# Parallel_Input.net
KiCad netlist of a schematic drawn in Altium Designer
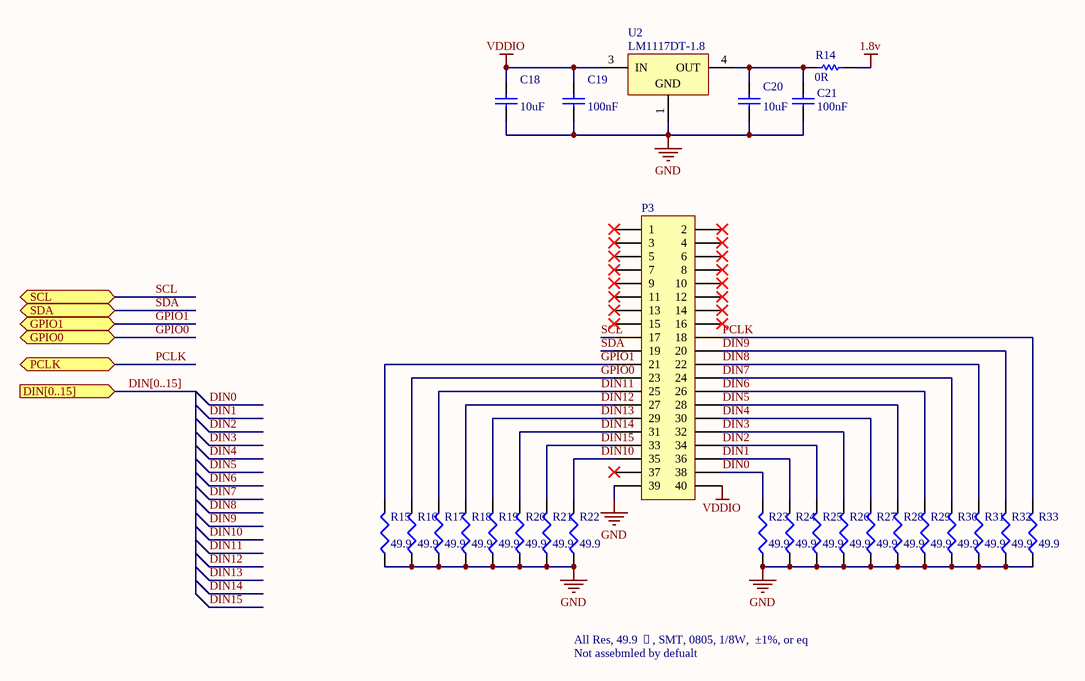
[diagram p0: Parallel Input.SchDoc]

(export (version "E")
  (design (tool "Eeschema 10.0.6"))
  (components
    (comp (ref "C18")
      (value "10uF")
      (footprint "0805")
      (description "Capacitor")
      (fields (field (name "PUBLISHER") "Altium Limited"))
      (libsource (lib "Miscellaneous Devices") (part "Cap"))
    )
    (comp (ref "C19")
      (value "100nF")
      (footprint "0603")
      (description "Capacitor")
      (fields (field (name "PUBLISHER") "Altium Limited"))
      (libsource (lib "Miscellaneous Devices") (part "Cap"))
    )
    (comp (ref "C20")
      (value "10uF")
      (footprint "0805")
      (description "Capacitor")
      (fields (field (name "PUBLISHER") "Altium Limited"))
      (libsource (lib "Miscellaneous Devices") (part "Cap"))
    )
    (comp (ref "C21")
      (value "100nF")
      (footprint "0603")
      (description "Capacitor")
      (fields (field (name "PUBLISHER") "Altium Limited"))
      (libsource (lib "Miscellaneous Devices") (part "Cap"))
    )
    (comp (ref "P3")
      (value "WE-2,54mm_Box Header 61204020621")
      (footprint "61204020621")
      (description "WR-BHD 2.54mm Male SMT Box Header")
      (fields
        (field (name "MANUFACTURER") "Würth Elektronik eiSos GmbH")
        (field (name "PARTNO") "61204020621")
        (field (name "CREATED BY") "Karrer Zheng")
      )
      (libsource (lib "WE_WR-BHD_Box Header_2.54mm_rev15b") (part "WE-2,54mm_Box Header 61204020621"))
    )
    (comp (ref "R14")
      (value "0R")
      (footprint "0805")
      (description "Semiconductor Resistor")
      (fields (field (name "PUBLISHER") "Altium Limited"))
      (libsource (lib "Miscellaneous Devices") (part "Res Semi"))
    )
    (comp (ref "R15")
      (value "49.9")
      (footprint "12Z-2010")
      (description "Resistor")
      (fields (field (name "Comment") "Res3") (field (name "PUBLISHER") "Altium Limited"))
      (libsource (lib "Miscellaneous Devices") (part "Res3"))
    )
    (comp (ref "R16")
      (value "49.9")
      (footprint "12Z-2010")
      (description "Resistor")
      (fields (field (name "Comment") "Res3") (field (name "PUBLISHER") "Altium Limited"))
      (libsource (lib "Miscellaneous Devices") (part "Res3"))
    )
    (comp (ref "R17")
      (value "49.9")
      (footprint "12Z-2010")
      (description "Resistor")
      (fields (field (name "Comment") "Res3") (field (name "PUBLISHER") "Altium Limited"))
      (libsource (lib "Miscellaneous Devices") (part "Res3"))
    )
    (comp (ref "R18")
      (value "49.9")
      (footprint "12Z-2010")
      (description "Resistor")
      (fields (field (name "Comment") "Res3") (field (name "PUBLISHER") "Altium Limited"))
      (libsource (lib "Miscellaneous Devices") (part "Res3"))
    )
    (comp (ref "R19")
      (value "49.9")
      (footprint "12Z-2010")
      (description "Resistor")
      (fields (field (name "Comment") "Res3") (field (name "PUBLISHER") "Altium Limited"))
      (libsource (lib "Miscellaneous Devices") (part "Res3"))
    )
    (comp (ref "R20")
      (value "49.9")
      (footprint "12Z-2010")
      (description "Resistor")
      (fields (field (name "Comment") "Res3") (field (name "PUBLISHER") "Altium Limited"))
      (libsource (lib "Miscellaneous Devices") (part "Res3"))
    )
    (comp (ref "R21")
      (value "49.9")
      (footprint "12Z-2010")
      (description "Resistor")
      (fields (field (name "Comment") "Res3") (field (name "PUBLISHER") "Altium Limited"))
      (libsource (lib "Miscellaneous Devices") (part "Res3"))
    )
    (comp (ref "R22")
      (value "49.9")
      (footprint "12Z-2010")
      (description "Resistor")
      (fields (field (name "Comment") "Res3") (field (name "PUBLISHER") "Altium Limited"))
      (libsource (lib "Miscellaneous Devices") (part "Res3"))
    )
    (comp (ref "R23")
      (value "49.9")
      (footprint "12Z-2010")
      (description "Resistor")
      (fields (field (name "Comment") "Res3") (field (name "PUBLISHER") "Altium Limited"))
      (libsource (lib "Miscellaneous Devices") (part "Res3"))
    )
    (comp (ref "R24")
      (value "49.9")
      (footprint "12Z-2010")
      (description "Resistor")
      (fields (field (name "Comment") "Res3") (field (name "PUBLISHER") "Altium Limited"))
      (libsource (lib "Miscellaneous Devices") (part "Res3"))
    )
    (comp (ref "R25")
      (value "49.9")
      (footprint "12Z-2010")
      (description "Resistor")
      (fields (field (name "Comment") "Res3") (field (name "PUBLISHER") "Altium Limited"))
      (libsource (lib "Miscellaneous Devices") (part "Res3"))
    )
    (comp (ref "R26")
      (value "49.9")
      (footprint "12Z-2010")
      (description "Resistor")
      (fields (field (name "Comment") "Res3") (field (name "PUBLISHER") "Altium Limited"))
      (libsource (lib "Miscellaneous Devices") (part "Res3"))
    )
    (comp (ref "R27")
      (value "49.9")
      (footprint "12Z-2010")
      (description "Resistor")
      (fields (field (name "Comment") "Res3") (field (name "PUBLISHER") "Altium Limited"))
      (libsource (lib "Miscellaneous Devices") (part "Res3"))
    )
    (comp (ref "R28")
      (value "49.9")
      (footprint "12Z-2010")
      (description "Resistor")
      (fields (field (name "Comment") "Res3") (field (name "PUBLISHER") "Altium Limited"))
      (libsource (lib "Miscellaneous Devices") (part "Res3"))
    )
    (comp (ref "R29")
      (value "49.9")
      (footprint "12Z-2010")
      (description "Resistor")
      (fields (field (name "Comment") "Res3") (field (name "PUBLISHER") "Altium Limited"))
      (libsource (lib "Miscellaneous Devices") (part "Res3"))
    )
    (comp (ref "R30")
      (value "49.9")
      (footprint "12Z-2010")
      (description "Resistor")
      (fields (field (name "Comment") "Res3") (field (name "PUBLISHER") "Altium Limited"))
      (libsource (lib "Miscellaneous Devices") (part "Res3"))
    )
    (comp (ref "R31")
      (value "49.9")
      (footprint "12Z-2010")
      (description "Resistor")
      (fields (field (name "Comment") "Res3") (field (name "PUBLISHER") "Altium Limited"))
      (libsource (lib "Miscellaneous Devices") (part "Res3"))
    )
    (comp (ref "R32")
      (value "49.9")
      (footprint "12Z-2010")
      (description "Resistor")
      (fields (field (name "Comment") "Res3") (field (name "PUBLISHER") "Altium Limited"))
      (libsource (lib "Miscellaneous Devices") (part "Res3"))
    )
    (comp (ref "R33")
      (value "49.9")
      (footprint "12Z-2010")
      (description "Resistor")
      (fields (field (name "Comment") "Res3") (field (name "PUBLISHER") "Altium Limited"))
      (libsource (lib "Miscellaneous Devices") (part "Res3"))
    )
    (comp (ref "U2")
      (value "LM1117DT-1.8")
      (footprint "TD03B_N")
      (description "800mA Low-Dropout Linear Regulator, 3-pin TO-252")
      (fields
        (field (name "PARTNUMBER") "LM1117DT-3.3")
        (field (name "MANUFACTURER") "National Semiconductor")
        (field (name "PUBLISHER") "Altium Limited")
      )
      (libsource (lib "NSC LDO") (part "LM1117DT-3.3"))
    )
  )
  (nets
    (net (code "1") (name "/DIN0") (class "Default")
      (node (ref "P3") (pin "38") (pinfunction "38_38") (pintype "passive"))
      (node (ref "R23") (pin "2") (pinfunction "2_2") (pintype "passive"))
    )
    (net (code "2") (name "/DIN1") (class "Default")
      (node (ref "P3") (pin "36") (pinfunction "36_36") (pintype "passive"))
      (node (ref "R24") (pin "2") (pinfunction "2_2") (pintype "passive"))
    )
    (net (code "3") (name "/DIN2") (class "Default")
      (node (ref "P3") (pin "34") (pinfunction "34_34") (pintype "passive"))
      (node (ref "R25") (pin "2") (pinfunction "2_2") (pintype "passive"))
    )
    (net (code "4") (name "/DIN3") (class "Default")
      (node (ref "P3") (pin "32") (pinfunction "32_32") (pintype "passive"))
      (node (ref "R26") (pin "2") (pinfunction "2_2") (pintype "passive"))
    )
    (net (code "5") (name "/DIN4") (class "Default")
      (node (ref "P3") (pin "30") (pinfunction "30_30") (pintype "passive"))
      (node (ref "R27") (pin "2") (pinfunction "2_2") (pintype "passive"))
    )
    (net (code "6") (name "/DIN5") (class "Default")
      (node (ref "P3") (pin "28") (pinfunction "28_28") (pintype "passive"))
      (node (ref "R28") (pin "2") (pinfunction "2_2") (pintype "passive"))
    )
    (net (code "7") (name "/DIN6") (class "Default")
      (node (ref "P3") (pin "26") (pinfunction "26_26") (pintype "passive"))
      (node (ref "R29") (pin "2") (pinfunction "2_2") (pintype "passive"))
    )
    (net (code "8") (name "/DIN7") (class "Default")
      (node (ref "P3") (pin "24") (pinfunction "24_24") (pintype "passive"))
      (node (ref "R30") (pin "2") (pinfunction "2_2") (pintype "passive"))
    )
    (net (code "9") (name "/DIN8") (class "Default")
      (node (ref "P3") (pin "22") (pinfunction "22_22") (pintype "passive"))
      (node (ref "R31") (pin "2") (pinfunction "2_2") (pintype "passive"))
    )
    (net (code "10") (name "/DIN9") (class "Default")
      (node (ref "P3") (pin "20") (pinfunction "20_20") (pintype "passive"))
      (node (ref "R32") (pin "2") (pinfunction "2_2") (pintype "passive"))
    )
    (net (code "11") (name "/DIN10") (class "Default")
      (node (ref "P3") (pin "35") (pinfunction "35_35") (pintype "passive"))
      (node (ref "R22") (pin "2") (pinfunction "2_2") (pintype "passive"))
    )
    (net (code "12") (name "/DIN11") (class "Default")
      (node (ref "P3") (pin "25") (pinfunction "25_25") (pintype "passive"))
      (node (ref "R17") (pin "2") (pinfunction "2_2") (pintype "passive"))
    )
    (net (code "13") (name "/DIN12") (class "Default")
      (node (ref "P3") (pin "27") (pinfunction "27_27") (pintype "passive"))
      (node (ref "R18") (pin "2") (pinfunction "2_2") (pintype "passive"))
    )
    (net (code "14") (name "/DIN13") (class "Default")
      (node (ref "P3") (pin "29") (pinfunction "29_29") (pintype "passive"))
      (node (ref "R19") (pin "2") (pinfunction "2_2") (pintype "passive"))
    )
    (net (code "15") (name "/DIN14") (class "Default")
      (node (ref "P3") (pin "31") (pinfunction "31_31") (pintype "passive"))
      (node (ref "R20") (pin "2") (pinfunction "2_2") (pintype "passive"))
    )
    (net (code "16") (name "/DIN15") (class "Default")
      (node (ref "P3") (pin "33") (pinfunction "33_33") (pintype "passive"))
      (node (ref "R21") (pin "2") (pinfunction "2_2") (pintype "passive"))
    )
    (net (code "18") (name "/GPIO0") (class "Default")
      (node (ref "P3") (pin "23") (pinfunction "23_23") (pintype "passive"))
      (node (ref "R16") (pin "2") (pinfunction "2_2") (pintype "passive"))
    )
    (net (code "19") (name "/GPIO1") (class "Default")
      (node (ref "P3") (pin "21") (pinfunction "21_21") (pintype "passive"))
      (node (ref "R15") (pin "2") (pinfunction "2_2") (pintype "passive"))
    )
    (net (code "20") (name "/PCLK") (class "Default")
      (node (ref "P3") (pin "18") (pinfunction "18_18") (pintype "passive"))
      (node (ref "R33") (pin "2") (pinfunction "2_2") (pintype "passive"))
    )
    (net (code "21") (name "/SCL") (class "Default")
      (node (ref "P3") (pin "17") (pinfunction "17_17") (pintype "passive"))
    )
    (net (code "22") (name "/SDA") (class "Default")
      (node (ref "P3") (pin "19") (pinfunction "19_19") (pintype "passive"))
    )
    (net (code "23") (name "1.8v") (class "Default")
      (node (ref "R14") (pin "2") (pinfunction "2_2") (pintype "passive"))
    )
    (net (code "24") (name "GND") (class "Default")
      (node (ref "C18") (pin "2") (pinfunction "2_2") (pintype "passive"))
      (node (ref "C19") (pin "2") (pinfunction "2_2") (pintype "passive"))
      (node (ref "C20") (pin "2") (pinfunction "2_2") (pintype "passive"))
      (node (ref "C21") (pin "2") (pinfunction "2_2") (pintype "passive"))
      (node (ref "P3") (pin "39") (pinfunction "39_39") (pintype "passive"))
      (node (ref "R15") (pin "1") (pinfunction "1_1") (pintype "passive"))
      (node (ref "R16") (pin "1") (pinfunction "1_1") (pintype "passive"))
      (node (ref "R17") (pin "1") (pinfunction "1_1") (pintype "passive"))
      (node (ref "R18") (pin "1") (pinfunction "1_1") (pintype "passive"))
      (node (ref "R19") (pin "1") (pinfunction "1_1") (pintype "passive"))
      (node (ref "R20") (pin "1") (pinfunction "1_1") (pintype "passive"))
      (node (ref "R21") (pin "1") (pinfunction "1_1") (pintype "passive"))
      (node (ref "R22") (pin "1") (pinfunction "1_1") (pintype "passive"))
      (node (ref "R23") (pin "1") (pinfunction "1_1") (pintype "passive"))
      (node (ref "R24") (pin "1") (pinfunction "1_1") (pintype "passive"))
      (node (ref "R25") (pin "1") (pinfunction "1_1") (pintype "passive"))
      (node (ref "R26") (pin "1") (pinfunction "1_1") (pintype "passive"))
      (node (ref "R27") (pin "1") (pinfunction "1_1") (pintype "passive"))
      (node (ref "R28") (pin "1") (pinfunction "1_1") (pintype "passive"))
      (node (ref "R29") (pin "1") (pinfunction "1_1") (pintype "passive"))
      (node (ref "R30") (pin "1") (pinfunction "1_1") (pintype "passive"))
      (node (ref "R31") (pin "1") (pinfunction "1_1") (pintype "passive"))
      (node (ref "R32") (pin "1") (pinfunction "1_1") (pintype "passive"))
      (node (ref "R33") (pin "1") (pinfunction "1_1") (pintype "passive"))
      (node (ref "U2") (pin "1") (pinfunction "GND_1") (pintype "power_in"))
    )
    (net (code "25") (name "Net-(U2-OUT)") (class "Default")
      (node (ref "C20") (pin "1") (pinfunction "1_1") (pintype "passive"))
      (node (ref "C21") (pin "1") (pinfunction "1_1") (pintype "passive"))
      (node (ref "R14") (pin "1") (pinfunction "1_1") (pintype "passive"))
      (node (ref "U2") (pin "4") (pinfunction "OUT_4") (pintype "power_in"))
    )
    (net (code "26") (name "VDDIO") (class "Default")
      (node (ref "C18") (pin "1") (pinfunction "1_1") (pintype "passive"))
      (node (ref "C19") (pin "1") (pinfunction "1_1") (pintype "passive"))
      (node (ref "P3") (pin "40") (pinfunction "40_40") (pintype "passive"))
      (node (ref "U2") (pin "3") (pinfunction "IN_3") (pintype "power_in"))
    )
    (net (code "27") (name "unconnected-(P3-Pad1)") (class "Default")
      (node (ref "P3") (pin "1") (pinfunction "1_1") (pintype "passive+no_connect"))
    )
    (net (code "28") (name "unconnected-(P3-Pad2)") (class "Default")
      (node (ref "P3") (pin "2") (pinfunction "2_2") (pintype "passive+no_connect"))
    )
    (net (code "29") (name "unconnected-(P3-Pad3)") (class "Default")
      (node (ref "P3") (pin "3") (pinfunction "3_3") (pintype "passive+no_connect"))
    )
    (net (code "30") (name "unconnected-(P3-Pad4)") (class "Default")
      (node (ref "P3") (pin "4") (pinfunction "4_4") (pintype "passive+no_connect"))
    )
    (net (code "31") (name "unconnected-(P3-Pad5)") (class "Default")
      (node (ref "P3") (pin "5") (pinfunction "5_5") (pintype "passive+no_connect"))
    )
    (net (code "32") (name "unconnected-(P3-Pad6)") (class "Default")
      (node (ref "P3") (pin "6") (pinfunction "6_6") (pintype "passive+no_connect"))
    )
    (net (code "33") (name "unconnected-(P3-Pad7)") (class "Default")
      (node (ref "P3") (pin "7") (pinfunction "7_7") (pintype "passive+no_connect"))
    )
    (net (code "34") (name "unconnected-(P3-Pad8)") (class "Default")
      (node (ref "P3") (pin "8") (pinfunction "8_8") (pintype "passive+no_connect"))
    )
    (net (code "35") (name "unconnected-(P3-Pad9)") (class "Default")
      (node (ref "P3") (pin "9") (pinfunction "9_9") (pintype "passive+no_connect"))
    )
    (net (code "36") (name "unconnected-(P3-Pad10)") (class "Default")
      (node (ref "P3") (pin "10") (pinfunction "10_10") (pintype "passive+no_connect"))
    )
    (net (code "37") (name "unconnected-(P3-Pad11)") (class "Default")
      (node (ref "P3") (pin "11") (pinfunction "11_11") (pintype "passive+no_connect"))
    )
    (net (code "38") (name "unconnected-(P3-Pad12)") (class "Default")
      (node (ref "P3") (pin "12") (pinfunction "12_12") (pintype "passive+no_connect"))
    )
    (net (code "39") (name "unconnected-(P3-Pad13)") (class "Default")
      (node (ref "P3") (pin "13") (pinfunction "13_13") (pintype "passive+no_connect"))
    )
    (net (code "40") (name "unconnected-(P3-Pad14)") (class "Default")
      (node (ref "P3") (pin "14") (pinfunction "14_14") (pintype "passive+no_connect"))
    )
    (net (code "41") (name "unconnected-(P3-Pad15)") (class "Default")
      (node (ref "P3") (pin "15") (pinfunction "15_15") (pintype "passive+no_connect"))
    )
    (net (code "42") (name "unconnected-(P3-Pad16)") (class "Default")
      (node (ref "P3") (pin "16") (pinfunction "16_16") (pintype "passive+no_connect"))
    )
    (net (code "43") (name "unconnected-(P3-Pad37)") (class "Default")
      (node (ref "P3") (pin "37") (pinfunction "37_37") (pintype "passive+no_connect"))
    )
  )
)
